# USB_C_PD.net
KiCad netlist of a schematic drawn in Altium Designer
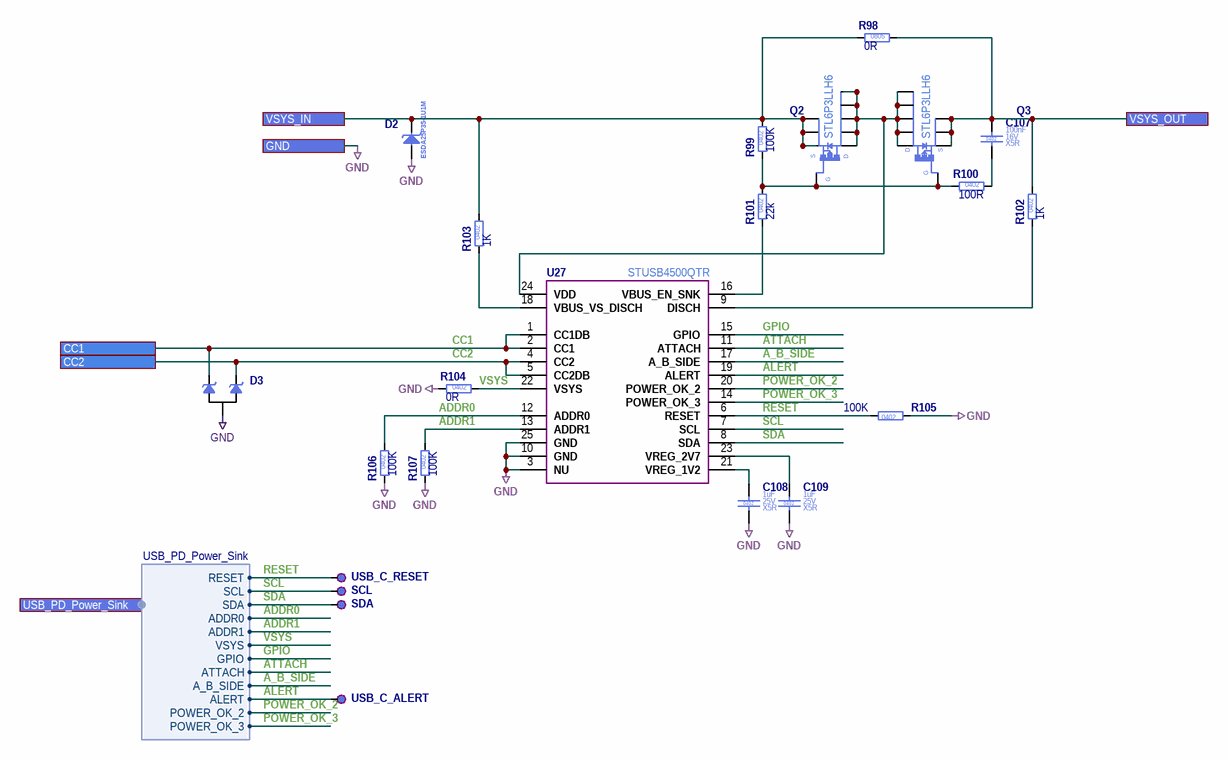
[diagram p0: USB_C_PD.SchDoc]

(export (version "E")
  (design (tool "Eeschema 10.0.6"))
  (components
    (comp (ref "C107")
      (value "C_100NF_16V_X5R_0402_10")
      (footprint "C_0402_1005")
      (description "Ceramic Capacitor")
      (fields
        (field (name "CASE/PACKAGE") "0402")
        (field (name "VOLTAGE RATING (DC)") "16V")
        (field (name "DIELECTRIC") "X5R")
        (field (name "CAPACITANCE") "100nF")
        (field (name "TOLERANCE") "10%")
        (field (name "MANUFACTURER PART NUMBER") "EMK105BJ104KV-F")
      )
      (libsource (lib "7Sigma") (part "C"))
    )
    (comp (ref "C108")
      (value "C_1UF_25V_X5R_0402_10")
      (footprint "C_0402_1005")
      (description "Ceramic Capacitor")
      (fields
        (field (name "CASE/PACKAGE") "0402")
        (field (name "VOLTAGE RATING (DC)") "25V")
        (field (name "DIELECTRIC") "X5R")
        (field (name "CAPACITANCE") "1uF")
        (field (name "TOLERANCE") "10%")
        (field (name "MANUFACTURER PART NUMBER") "CL05A105KA5NQNC")
      )
      (libsource (lib "7Sigma") (part "C"))
    )
    (comp (ref "C109")
      (value "C_1UF_25V_X5R_0402_10")
      (footprint "C_0402_1005")
      (description "Ceramic Capacitor")
      (fields
        (field (name "CASE/PACKAGE") "0402")
        (field (name "VOLTAGE RATING (DC)") "25V")
        (field (name "DIELECTRIC") "X5R")
        (field (name "CAPACITANCE") "1uF")
        (field (name "TOLERANCE") "10%")
        (field (name "MANUFACTURER PART NUMBER") "CL05A105KA5NQNC")
      )
      (libsource (lib "7Sigma") (part "C"))
    )
    (comp (ref "D2")
      (value "ESDA25P35-1U1M")
      (footprint "TVS_0603_1610")
      (description "High power transient voltage suppressor")
      (fields
        (field (name "PART NUMBER") "ESDA25P35-1U1M")
        (field (name "MANUFACTURER") "STMicroelectronics")
      )
      (libsource (lib "7Sigma") (part "TVS_UNI"))
    )
    (comp (ref "D3")
      (value "ESDA25W")
      (footprint "SOT323_SC70")
      (description "TVS DIODE 24VWM SOT23")
      (fields (field (name "MANUFACTURER") "STMicroelectronics"))
      (libsource (lib "7Sigma") (part "TVS_DOUBLE_SOT23-3"))
    )
    (comp (ref "Q2")
      (value "STL6P3LLH6")
      (footprint "PQFN65P330X332X105_HS-9N")
      (description "P-MOSFET 30V 6A 24mOhm")
      (fields
        (field (name "MANUFACTURER") "STMicroelectronics")
        (field (name "MANUFACTURER PART NUMBER") "STL6P3LLH6")
      )
      (libsource (lib "") (part "STL6P3LLH6_1"))
    )
    (comp (ref "Q3")
      (value "STL6P3LLH6")
      (footprint "PQFN65P330X332X105_HS-9N")
      (description "P-MOSFET 30V 6A 24mOhm")
      (fields
        (field (name "MANUFACTURER") "STMicroelectronics")
        (field (name "MANUFACTURER PART NUMBER") "STL6P3LLH6")
      )
      (libsource (lib "7Sigma") (part "STL6P3LLH6"))
    )
    (comp (ref "R98")
      (value "R_0R_0805_1")
      (footprint "R_0805_2012")
      (description "Thick Film Resistor")
      (fields
        (field (name "RESISTANCE") "0R")
        (field (name "CASE/PACKAGE") "0805")
        (field (name "TOLERANCE") "5%")
        (field (name "MANUFACTURER") "Yageo")
      )
      (libsource (lib "7Sigma") (part "R"))
    )
    (comp (ref "R99")
      (value "R_100K_0402_1")
      (footprint "R_0402_1005")
      (description "Thick Film Resistor")
      (fields
        (field (name "RESISTANCE") "100K")
        (field (name "CASE/PACKAGE") "0402")
        (field (name "TOLERANCE") "1%")
        (field (name "MANUFACTURER") "Yageo")
      )
      (libsource (lib "7Sigma") (part "R"))
    )
    (comp (ref "R100")
      (value "R_100R_0402_1")
      (footprint "R_0402_1005")
      (description "Thick Film Resistor")
      (fields
        (field (name "RESISTANCE") "100R")
        (field (name "CASE/PACKAGE") "0402")
        (field (name "TOLERANCE") "1%")
        (field (name "MANUFACTURER") "Yageo")
      )
      (libsource (lib "7Sigma") (part "R"))
    )
    (comp (ref "R101")
      (value "R_22K_0402_1")
      (footprint "R_0402_1005")
      (description "Thick Film resistor")
      (fields
        (field (name "RESISTANCE") "22k")
        (field (name "CASE/PACKAGE") "0402")
        (field (name "TOLERANCE") "1%")
        (field (name "MANUFACTURER") "Yageo")
      )
      (libsource (lib "7Sigma") (part "R"))
    )
    (comp (ref "R102")
      (value "R_1K_0402_1")
      (footprint "R_0402_1005")
      (description "Thick Film Resistor")
      (fields
        (field (name "RESISTANCE") "1K")
        (field (name "CASE/PACKAGE") "0402")
        (field (name "TOLERANCE") "1%")
        (field (name "MANUFACTURER") "Yageo")
      )
      (libsource (lib "7Sigma") (part "R"))
    )
    (comp (ref "R103")
      (value "R_1K_0402_1")
      (footprint "R_0402_1005")
      (description "Thick Film Resistor")
      (fields
        (field (name "RESISTANCE") "1K")
        (field (name "CASE/PACKAGE") "0402")
        (field (name "TOLERANCE") "1%")
        (field (name "MANUFACTURER") "Yageo")
      )
      (libsource (lib "7Sigma") (part "R"))
    )
    (comp (ref "R104")
      (value "R_0R_0402_1")
      (footprint "R_0402_1005")
      (description "Thick Film Resistor")
      (fields
        (field (name "RESISTANCE") "0R")
        (field (name "CASE/PACKAGE") "0402")
        (field (name "TOLERANCE") "1%")
        (field (name "MANUFACTURER") "Yageo")
      )
      (libsource (lib "7Sigma") (part "R"))
    )
    (comp (ref "R105")
      (value "R_100K_0402_1")
      (footprint "R_0402_1005")
      (description "Thick Film Resistor")
      (fields
        (field (name "RESISTANCE") "100K")
        (field (name "CASE/PACKAGE") "0402")
        (field (name "TOLERANCE") "1%")
        (field (name "MANUFACTURER") "Yageo")
      )
      (libsource (lib "7Sigma") (part "R"))
    )
    (comp (ref "R106")
      (value "R_100K_0402_1")
      (footprint "R_0402_1005")
      (description "Thick Film Resistor")
      (fields
        (field (name "RESISTANCE") "100K")
        (field (name "CASE/PACKAGE") "0402")
        (field (name "TOLERANCE") "1%")
        (field (name "MANUFACTURER") "Yageo")
      )
      (libsource (lib "7Sigma") (part "R"))
    )
    (comp (ref "R107")
      (value "R_100K_0402_1")
      (footprint "R_0402_1005")
      (description "Thick Film Resistor")
      (fields
        (field (name "RESISTANCE") "100K")
        (field (name "CASE/PACKAGE") "0402")
        (field (name "TOLERANCE") "1%")
        (field (name "MANUFACTURER") "Yageo")
      )
      (libsource (lib "7Sigma") (part "R"))
    )
    (comp (ref "SCL")
      (value "TP_PAD_1.3MM")
      (footprint "TP_PAD_1.3MM")
      (description "Testpoint SMD 1.3mm")
      (libsource (lib "7Sigma") (part "TESTPOINT"))
    )
    (comp (ref "SDA")
      (value "TP_PAD_1.3MM")
      (footprint "TP_PAD_1.3MM")
      (description "Testpoint SMD 1.3mm")
      (libsource (lib "7Sigma") (part "TESTPOINT"))
    )
    (comp (ref "U27")
      (value "STUSB4500QTR")
      (footprint "QFN50P400X400X100_HS-25N")
      (description "Standalone USB PD controller for power sinking devices")
      (fields
        (field (name "MANUFACTURER PART NUMBER") "STUSB4500QTR")
        (field (name "MANUFACTURER") "STMicroelectronics")
      )
      (libsource (lib "7Sigma") (part "STUSB4500QTR"))
    )
    (comp (ref "USB_C_ALERT")
      (value "TP_PAD_1.3MM")
      (footprint "TP_PAD_1.3MM")
      (description "Testpoint SMD 1.3mm")
      (libsource (lib "7Sigma") (part "TESTPOINT"))
    )
    (comp (ref "USB_C_RESET")
      (value "TP_PAD_1.3MM")
      (footprint "TP_PAD_1.3MM")
      (description "Testpoint SMD 1.3mm")
      (libsource (lib "7Sigma") (part "TESTPOINT"))
    )
  )
  (nets
    (net (code "2") (name "/ADDR0") (class "Default")
      (node (ref "R106") (pin "2") (pinfunction "2_2") (pintype "passive"))
      (node (ref "U27") (pin "12") (pinfunction "ADDR0_12") (pintype "passive"))
    )
    (net (code "3") (name "/ADDR1") (class "Default")
      (node (ref "R107") (pin "2") (pinfunction "2_2") (pintype "passive"))
      (node (ref "U27") (pin "13") (pinfunction "ADDR1_13") (pintype "passive"))
    )
    (net (code "4") (name "/ALERT") (class "Default")
      (node (ref "U27") (pin "19") (pinfunction "ALERT_19") (pintype "passive"))
      (node (ref "USB_C_ALERT") (pin "1") (pinfunction "TP_1") (pintype "passive"))
    )
    (net (code "5") (name "/ATTACH") (class "Default")
      (node (ref "U27") (pin "11") (pinfunction "ATTACH_11") (pintype "passive"))
    )
    (net (code "6") (name "/A_B_SIDE") (class "Default")
      (node (ref "U27") (pin "17") (pinfunction "A_B_SIDE_17") (pintype "passive"))
    )
    (net (code "7") (name "/CC1") (class "Default")
      (node (ref "D3") (pin "1") (pinfunction "100_1") (pintype "passive"))
      (node (ref "U27") (pin "1") (pinfunction "CC1DB_1") (pintype "passive"))
      (node (ref "U27") (pin "2") (pinfunction "CC1_2") (pintype "passive"))
    )
    (net (code "8") (name "/CC2") (class "Default")
      (node (ref "D3") (pin "2") (pintype "passive"))
      (node (ref "U27") (pin "4") (pinfunction "CC2_4") (pintype "passive"))
      (node (ref "U27") (pin "5") (pinfunction "CC2DB_5") (pintype "passive"))
    )
    (net (code "9") (name "/GPIO") (class "Default")
      (node (ref "U27") (pin "15") (pinfunction "GPIO_15") (pintype "passive"))
    )
    (net (code "10") (name "/POWER_OK_2") (class "Default")
      (node (ref "U27") (pin "20") (pinfunction "POWER_OK_2_20") (pintype "passive"))
    )
    (net (code "11") (name "/POWER_OK_3") (class "Default")
      (node (ref "U27") (pin "14") (pinfunction "POWER_OK_3_14") (pintype "passive"))
    )
    (net (code "12") (name "/RESET") (class "Default")
      (node (ref "R105") (pin "2") (pinfunction "2_2") (pintype "passive"))
      (node (ref "U27") (pin "6") (pinfunction "RESET_6") (pintype "passive"))
      (node (ref "USB_C_RESET") (pin "1") (pinfunction "TP_1") (pintype "passive"))
    )
    (net (code "13") (name "/SCL") (class "Default")
      (node (ref "SCL") (pin "1") (pinfunction "TP_1") (pintype "passive"))
      (node (ref "U27") (pin "7") (pinfunction "SCL_7") (pintype "passive"))
    )
    (net (code "14") (name "/SDA") (class "Default")
      (node (ref "SDA") (pin "1") (pinfunction "TP_1") (pintype "passive"))
      (node (ref "U27") (pin "8") (pinfunction "SDA_8") (pintype "passive"))
    )
    (net (code "15") (name "/VSYS") (class "Default")
      (node (ref "R104") (pin "2") (pinfunction "2_2") (pintype "passive"))
      (node (ref "U27") (pin "22") (pinfunction "VSYS_22") (pintype "passive"))
    )
    (net (code "16") (name "/VSYS_IN") (class "Default")
      (node (ref "D2") (pin "1") (pinfunction "C_1") (pintype "passive"))
      (node (ref "Q2") (pin "1") (pinfunction "S_1") (pintype "passive"))
      (node (ref "Q2") (pin "2") (pinfunction "S_2") (pintype "passive"))
      (node (ref "Q2") (pin "3") (pinfunction "S_3") (pintype "passive"))
      (node (ref "R103") (pin "2") (pinfunction "2_2") (pintype "passive"))
      (node (ref "R98") (pin "1") (pinfunction "1_1") (pintype "passive"))
      (node (ref "R99") (pin "2") (pinfunction "2_2") (pintype "passive"))
    )
    (net (code "17") (name "/VSYS_OUT") (class "Default")
      (node (ref "C107") (pin "1") (pinfunction "1_1") (pintype "passive"))
      (node (ref "Q3") (pin "1") (pinfunction "S_1") (pintype "passive"))
      (node (ref "Q3") (pin "2") (pinfunction "S_2") (pintype "passive"))
      (node (ref "Q3") (pin "3") (pinfunction "S_3") (pintype "passive"))
      (node (ref "R102") (pin "2") (pinfunction "2_2") (pintype "passive"))
      (node (ref "R98") (pin "2") (pinfunction "2_2") (pintype "passive"))
    )
    (net (code "19") (name "GND") (class "Default")
      (node (ref "C108") (pin "2") (pinfunction "2_2") (pintype "passive"))
      (node (ref "C109") (pin "2") (pinfunction "2_2") (pintype "passive"))
      (node (ref "D2") (pin "2") (pinfunction "A_2") (pintype "passive"))
      (node (ref "D3") (pin "3") (pintype "passive"))
      (node (ref "R104") (pin "1") (pinfunction "1_1") (pintype "passive"))
      (node (ref "R105") (pin "1") (pinfunction "1_1") (pintype "passive"))
      (node (ref "R106") (pin "1") (pinfunction "1_1") (pintype "passive"))
      (node (ref "R107") (pin "1") (pinfunction "1_1") (pintype "passive"))
      (node (ref "U27") (pin "10") (pinfunction "GND_10") (pintype "passive"))
      (node (ref "U27") (pin "25") (pinfunction "GND_25") (pintype "passive"))
      (node (ref "U27") (pin "3") (pinfunction "NU_3") (pintype "passive"))
    )
    (net (code "20") (name "Net-(C107-Pad2)") (class "Default")
      (node (ref "C107") (pin "2") (pinfunction "2_2") (pintype "passive"))
      (node (ref "R100") (pin "2") (pinfunction "2_2") (pintype "passive"))
    )
    (net (code "21") (name "Net-(Q2-G)") (class "Default")
      (node (ref "Q2") (pin "4") (pinfunction "G_4") (pintype "passive"))
      (node (ref "Q3") (pin "4") (pinfunction "G_4") (pintype "passive"))
      (node (ref "R100") (pin "1") (pinfunction "1_1") (pintype "passive"))
      (node (ref "R101") (pin "2") (pinfunction "2_2") (pintype "passive"))
      (node (ref "R99") (pin "1") (pinfunction "1_1") (pintype "passive"))
    )
    (net (code "22") (name "Net-(U27-DISCH)") (class "Default")
      (node (ref "R102") (pin "1") (pinfunction "1_1") (pintype "passive"))
      (node (ref "U27") (pin "9") (pinfunction "DISCH_9") (pintype "passive"))
    )
    (net (code "23") (name "Net-(U27-VBUS_EN_SNK)") (class "Default")
      (node (ref "R101") (pin "1") (pinfunction "1_1") (pintype "passive"))
      (node (ref "U27") (pin "16") (pinfunction "VBUS_EN_SNK_16") (pintype "passive"))
    )
    (net (code "24") (name "Net-(U27-VBUS_VS_DISCH)") (class "Default")
      (node (ref "R103") (pin "1") (pinfunction "1_1") (pintype "passive"))
      (node (ref "U27") (pin "18") (pinfunction "VBUS_VS_DISCH_18") (pintype "passive"))
    )
    (net (code "25") (name "Net-(U27-VDD)") (class "Default")
      (node (ref "Q2") (pin "5") (pinfunction "D_5") (pintype "passive"))
      (node (ref "Q2") (pin "6") (pinfunction "D_6") (pintype "passive"))
      (node (ref "Q2") (pin "7") (pinfunction "D_7") (pintype "passive"))
      (node (ref "Q2") (pin "8") (pinfunction "D_8") (pintype "passive"))
      (node (ref "Q2") (pin "9") (pinfunction "D_9") (pintype "passive"))
      (node (ref "Q3") (pin "5") (pinfunction "D_5") (pintype "passive"))
      (node (ref "Q3") (pin "6") (pinfunction "D_6") (pintype "passive"))
      (node (ref "Q3") (pin "7") (pinfunction "D_7") (pintype "passive"))
      (node (ref "Q3") (pin "8") (pinfunction "D_8") (pintype "passive"))
      (node (ref "Q3") (pin "9") (pinfunction "D_9") (pintype "passive"))
      (node (ref "U27") (pin "24") (pinfunction "VDD_24") (pintype "passive"))
    )
    (net (code "26") (name "Net-(U27-VREG_1V2)") (class "Default")
      (node (ref "C108") (pin "1") (pinfunction "1_1") (pintype "passive"))
      (node (ref "U27") (pin "21") (pinfunction "VREG_1V2_21") (pintype "passive"))
    )
    (net (code "27") (name "Net-(U27-VREG_2V7)") (class "Default")
      (node (ref "C109") (pin "1") (pinfunction "1_1") (pintype "passive"))
      (node (ref "U27") (pin "23") (pinfunction "VREG_2V7_23") (pintype "passive"))
    )
  )
)
